# AB_Amplifier.net
KiCad netlist of a schematic drawn in Altium Designer
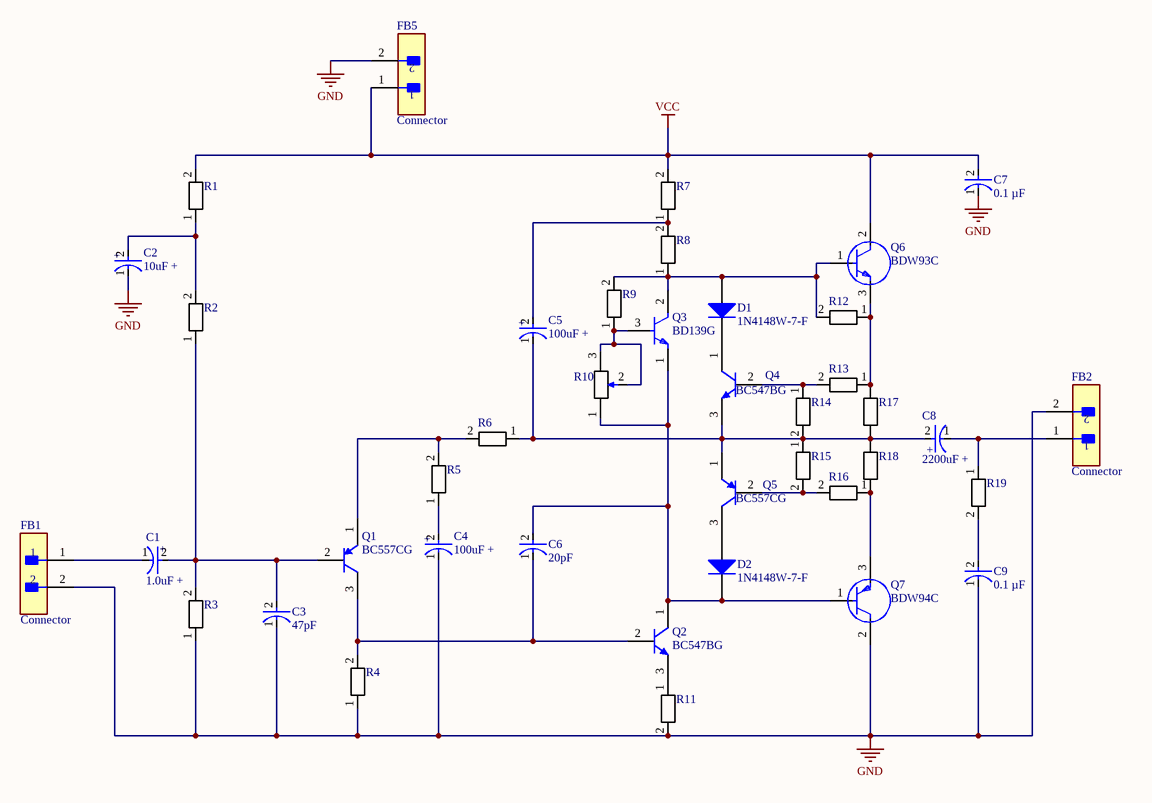
[diagram p0: AB_Amplifier.SchDoc]

(export (version "E")
  (design (tool "Eeschema 10.0.6"))
  (components
    (comp (ref "C1")
      (value "1.0uF +")
      (footprint "106CKR050M")
      (libsource (lib "AB-Amplifier") (part "Elco - 1.0uF"))
    )
    (comp (ref "C2")
      (value "10uF +")
      (footprint "106CKR050M")
      (libsource (lib "AB-Amplifier") (part "Elco - 10uF"))
    )
    (comp (ref "C3")
      (value "47pF")
      (footprint "0805")
      (libsource (lib "AB-Amplifier") (part "Capasitor - 0805"))
    )
    (comp (ref "C4")
      (value "100uF +")
      (footprint "107CKR050M")
      (libsource (lib "AB-Amplifier") (part "Elco - 100uF"))
    )
    (comp (ref "C5")
      (value "100uF +")
      (footprint "107CKR050M")
      (libsource (lib "AB-Amplifier") (part "Elco - 100uF"))
    )
    (comp (ref "C6")
      (value "20pF")
      (footprint "0805")
      (libsource (lib "AB-Amplifier") (part "Capasitor - 0805"))
    )
    (comp (ref "C7")
      (value "0.1 µF")
      (footprint "0805")
      (libsource (lib "AB-Amplifier") (part "Capasitor - 0805"))
    )
    (comp (ref "C8")
      (value "2200uF +")
      (footprint "2200cap")
      (libsource (lib "AB-Amplifier") (part "Elco - 2000uF"))
    )
    (comp (ref "C9")
      (value "0.1 µF")
      (footprint "0805")
      (libsource (lib "AB-Amplifier") (part "Capasitor - 0805"))
    )
    (comp (ref "D1")
      (value "1N4148W-7-F")
      (footprint "1N4148")
      (description "Fast Switching Diode, 100 V, 0.15 A, -65 to 150 degC, 2-Pin?SOD123, RoHS, Tape and Reel")
      (fields (field (name "MANUFACTURER") "DiodesIncorporated"))
      (libsource (lib "AB-Amplifier") (part "Diode - 1N4148"))
    )
    (comp (ref "D2")
      (value "1N4148W-7-F")
      (footprint "1N4148")
      (description "Fast Switching Diode, 100 V, 0.15 A, -65 to 150 degC, 2-Pin?SOD123, RoHS, Tape and Reel")
      (fields (field (name "MANUFACTURER") "DiodesIncorporated"))
      (libsource (lib "AB-Amplifier") (part "Diode - 1N4148"))
    )
    (comp (ref "FB1")
      (value "Connector")
      (footprint "AB-Amplifier:Connector")
      (description "Ferrite Bead")
      (fields
        (field (name "MANUFACTURER_PART_NUMBER") "ACML-0805-500-T")
        (field (name "MOUSER PART NUMBER") "815-ACML-0805-500T")
      )
      (libsource (lib "") (part "Connector_1"))
    )
    (comp (ref "FB2")
      (value "Connector")
      (footprint "AB-Amplifier:Connector")
      (description "Ferrite Bead")
      (fields
        (field (name "MANUFACTURER_PART_NUMBER") "ACML-0805-500-T")
        (field (name "MOUSER PART NUMBER") "815-ACML-0805-500T")
      )
      (libsource (lib "AB-Amplifier") (part "Connector"))
    )
    (comp (ref "FB5")
      (value "Connector")
      (footprint "AB-Amplifier:Connector")
      (description "Ferrite Bead")
      (fields
        (field (name "MANUFACTURER_PART_NUMBER") "ACML-0805-500-T")
        (field (name "MOUSER PART NUMBER") "815-ACML-0805-500T")
      )
      (libsource (lib "AB-Amplifier") (part "Connector"))
    )
    (comp (ref "Q1")
      (value "BC557CG")
      (footprint "BC557")
      (description "Amplifier Transistor, PNP Silicon, 3-Pin TO-92, Pb-Free, Bulk Box")
      (fields (field (name "MANUFACTURER") "On Semiconductor"))
      (libsource (lib "AB-Amplifier") (part "Transistor - BC557_1"))
    )
    (comp (ref "Q2")
      (value "BC547BG")
      (footprint "BC547")
      (description "Amplifier Transistor, NPN Silicon, 3-Pin TO-92, Pb-Free, Bulk Box")
      (fields (field (name "MANUFACTURER") "On Semiconductor"))
      (libsource (lib "AB-Amplifier") (part "Transistor - BC547_1"))
    )
    (comp (ref "Q3")
      (value "BD139G")
      (footprint "BD139")
      (libsource (lib "AB-Amplifier") (part "Transistor - BD139"))
    )
    (comp (ref "Q4")
      (value "BC547BG")
      (footprint "BC547")
      (description "Amplifier Transistor, NPN Silicon, 3-Pin TO-92, Pb-Free, Bulk Box")
      (fields (field (name "MANUFACTURER") "On Semiconductor"))
      (libsource (lib "AB-Amplifier") (part "Transistor - BC547"))
    )
    (comp (ref "Q5")
      (value "BC557CG")
      (footprint "BC557")
      (description "Amplifier Transistor, PNP Silicon, 3-Pin TO-92, Pb-Free, Bulk Box")
      (fields (field (name "MANUFACTURER") "On Semiconductor"))
      (libsource (lib "AB-Amplifier") (part "Transistor - BC557"))
    )
    (comp (ref "Q6")
      (value "BDW93C")
      (footprint "BDW94C")
      (description "BDW93C BDW93C Series 100 V 12 A 80 W NPN Darlington Transistor - TO-220-3")
      (libsource (lib "AB-Amplifier") (part "Transistor - BDW93C"))
    )
    (comp (ref "Q7")
      (value "BDW94C")
      (footprint "AB-Amplifier:BDW94C")
      (description "Transistor BJT PNP")
      (fields (field (name "MOUSER PART NUMBER") "511-BDW94C"))
      (libsource (lib "AB-Amplifier") (part "Transistor - BDW94C"))
    )
    (comp (ref "R1")
      (value "CRCW080510R0FKEA")
      (footprint "0805")
      (fields (field (name "MANUFACTURER") "Vishay Dale"))
      (libsource (lib "AB-Amplifier") (part "Resistor 0805"))
    )
    (comp (ref "R2")
      (value "CRCW080510R0FKEA")
      (footprint "0805")
      (fields (field (name "MANUFACTURER") "Vishay Dale"))
      (libsource (lib "AB-Amplifier") (part "Resistor 0805"))
    )
    (comp (ref "R3")
      (value "CRCW080510R0FKEA")
      (footprint "0805")
      (fields (field (name "MANUFACTURER") "Vishay Dale"))
      (libsource (lib "AB-Amplifier") (part "Resistor 0805"))
    )
    (comp (ref "R4")
      (value "CRCW080510R0FKEA")
      (footprint "0805")
      (fields (field (name "MANUFACTURER") "Vishay Dale"))
      (libsource (lib "AB-Amplifier") (part "Resistor 0805"))
    )
    (comp (ref "R5")
      (value "CRCW080510R0FKEA")
      (footprint "0805")
      (fields (field (name "MANUFACTURER") "Vishay Dale"))
      (libsource (lib "AB-Amplifier") (part "Resistor 0805"))
    )
    (comp (ref "R6")
      (value "CRCW080510R0FKEA")
      (footprint "0805")
      (fields (field (name "MANUFACTURER") "Vishay Dale"))
      (libsource (lib "AB-Amplifier") (part "Resistor 0805"))
    )
    (comp (ref "R7")
      (value "CRCW080510R0FKEA")
      (footprint "0805")
      (fields (field (name "MANUFACTURER") "Vishay Dale"))
      (libsource (lib "AB-Amplifier") (part "Resistor 0805"))
    )
    (comp (ref "R8")
      (value "CRCW080510R0FKEA")
      (footprint "0805")
      (fields (field (name "MANUFACTURER") "Vishay Dale"))
      (libsource (lib "AB-Amplifier") (part "Resistor 0805"))
    )
    (comp (ref "R9")
      (value "CRCW080510R0FKEA")
      (footprint "0805")
      (fields (field (name "MANUFACTURER") "Vishay Dale"))
      (libsource (lib "AB-Amplifier") (part "Resistor 0805"))
    )
    (comp (ref "R10")
      (value "249FGJSPXB25503KA")
      (footprint "Potentiometer 15mm")
      (fields (field (name "TOLERANCE") "10%"))
      (libsource (lib "AB-Amplifier") (part "Potentiometer"))
    )
    (comp (ref "R11")
      (value "CRCW080510R0FKEA")
      (footprint "0805")
      (fields (field (name "MANUFACTURER") "Vishay Dale"))
      (libsource (lib "AB-Amplifier") (part "Resistor 0805"))
    )
    (comp (ref "R12")
      (value "CRCW080510R0FKEA")
      (footprint "0805")
      (fields (field (name "MANUFACTURER") "Vishay Dale"))
      (libsource (lib "AB-Amplifier") (part "Resistor 0805"))
    )
    (comp (ref "R13")
      (value "CRCW080510R0FKEA")
      (footprint "0805")
      (fields (field (name "MANUFACTURER") "Vishay Dale"))
      (libsource (lib "AB-Amplifier") (part "Resistor 0805"))
    )
    (comp (ref "R14")
      (value "CRCW080510R0FKEA")
      (footprint "0805")
      (fields (field (name "MANUFACTURER") "Vishay Dale"))
      (libsource (lib "AB-Amplifier") (part "Resistor 0805"))
    )
    (comp (ref "R15")
      (value "CRCW080510R0FKEA")
      (footprint "0805")
      (fields (field (name "MANUFACTURER") "Vishay Dale"))
      (libsource (lib "AB-Amplifier") (part "Resistor 0805"))
    )
    (comp (ref "R16")
      (value "CRCW080510R0FKEA")
      (footprint "0805")
      (fields (field (name "MANUFACTURER") "Vishay Dale"))
      (libsource (lib "AB-Amplifier") (part "Resistor 0805"))
    )
    (comp (ref "R17")
      (value "RK73B2ATTD224J")
      (footprint "0.33 1W")
      (fields (field (name "MANUFACTURER") "KOA Speer"))
      (libsource (lib "AB-Amplifier") (part "Resistor - 1W Through Hole"))
    )
    (comp (ref "R18")
      (value "RK73B2ATTD224J")
      (footprint "0.33 1W")
      (fields (field (name "MANUFACTURER") "KOA Speer"))
      (libsource (lib "AB-Amplifier") (part "Resistor - 1W Through Hole"))
    )
    (comp (ref "R19")
      (value "CRCW080510R0FKEA")
      (footprint "0805")
      (fields (field (name "MANUFACTURER") "Vishay Dale"))
      (libsource (lib "AB-Amplifier") (part "Resistor 0805"))
    )
  )
  (nets
    (net (code "1") (name "GND") (class "Default")
      (node (ref "C2") (pin "1") (pinfunction "C_1") (pintype "passive"))
      (node (ref "C3") (pin "1") (pinfunction "C_1") (pintype "passive"))
      (node (ref "C4") (pin "1") (pinfunction "C_1") (pintype "passive"))
      (node (ref "C7") (pin "1") (pinfunction "C_1") (pintype "passive"))
      (node (ref "C9") (pin "1") (pinfunction "C_1") (pintype "passive"))
      (node (ref "FB1") (pin "2") (pinfunction "2_2") (pintype "passive"))
      (node (ref "FB2") (pin "2") (pinfunction "2_2") (pintype "passive"))
      (node (ref "FB5") (pin "2") (pinfunction "2_2") (pintype "passive"))
      (node (ref "Q7") (pin "2") (pinfunction "C_2") (pintype "passive"))
      (node (ref "R11") (pin "2") (pinfunction "2_2") (pintype "passive"))
      (node (ref "R3") (pin "1") (pinfunction "1_1") (pintype "passive"))
      (node (ref "R4") (pin "1") (pinfunction "1_1") (pintype "passive"))
    )
    (net (code "2") (name "Net-(C1-A)") (class "Default")
      (node (ref "C1") (pin "2") (pinfunction "A_2") (pintype "passive"))
      (node (ref "C3") (pin "2") (pinfunction "A_2") (pintype "passive"))
      (node (ref "Q1") (pin "2") (pinfunction "B_2") (pintype "passive"))
      (node (ref "R2") (pin "1") (pinfunction "1_1") (pintype "passive"))
      (node (ref "R3") (pin "2") (pinfunction "2_2") (pintype "passive"))
    )
    (net (code "3") (name "Net-(C1-C)") (class "Default")
      (node (ref "C1") (pin "1") (pinfunction "C_1") (pintype "passive"))
      (node (ref "FB1") (pin "1") (pinfunction "1_1") (pintype "passive"))
    )
    (net (code "4") (name "Net-(C2-A)") (class "Default")
      (node (ref "C2") (pin "2") (pinfunction "A_2") (pintype "passive"))
      (node (ref "R1") (pin "1") (pinfunction "1_1") (pintype "passive"))
      (node (ref "R2") (pin "2") (pinfunction "2_2") (pintype "passive"))
    )
    (net (code "5") (name "Net-(C4-A)") (class "Default")
      (node (ref "C4") (pin "2") (pinfunction "A_2") (pintype "passive"))
      (node (ref "R5") (pin "1") (pinfunction "1_1") (pintype "passive"))
    )
    (net (code "6") (name "Net-(C5-A)") (class "Default")
      (node (ref "C5") (pin "2") (pinfunction "A_2") (pintype "passive"))
      (node (ref "R7") (pin "1") (pinfunction "1_1") (pintype "passive"))
      (node (ref "R8") (pin "2") (pinfunction "2_2") (pintype "passive"))
    )
    (net (code "7") (name "Net-(C5-C)") (class "Default")
      (node (ref "C5") (pin "1") (pinfunction "C_1") (pintype "passive"))
      (node (ref "C8") (pin "2") (pinfunction "A_2") (pintype "passive"))
      (node (ref "Q4") (pin "3") (pinfunction "E_3") (pintype "passive"))
      (node (ref "Q5") (pin "1") (pinfunction "E_1") (pintype "passive"))
      (node (ref "R14") (pin "2") (pinfunction "2_2") (pintype "passive"))
      (node (ref "R15") (pin "1") (pinfunction "1_1") (pintype "passive"))
      (node (ref "R17") (pin "1") (pinfunction "1_1") (pintype "passive"))
      (node (ref "R18") (pin "2") (pinfunction "2_2") (pintype "passive"))
      (node (ref "R6") (pin "1") (pinfunction "1_1") (pintype "passive"))
    )
    (net (code "8") (name "Net-(C6-A)") (class "Default")
      (node (ref "C6") (pin "2") (pinfunction "A_2") (pintype "passive"))
      (node (ref "D2") (pin "2") (pinfunction "K_2") (pintype "passive"))
      (node (ref "Q2") (pin "1") (pinfunction "C_1") (pintype "passive"))
      (node (ref "Q3") (pin "1") (pinfunction "E_1") (pintype "passive"))
      (node (ref "Q7") (pin "1") (pinfunction "B_1") (pintype "passive"))
      (node (ref "R10") (pin "1") (pinfunction "1_1") (pintype "passive"))
    )
    (net (code "9") (name "Net-(C6-C)") (class "Default")
      (node (ref "C6") (pin "1") (pinfunction "C_1") (pintype "passive"))
      (node (ref "Q1") (pin "3") (pinfunction "E_3") (pintype "passive"))
      (node (ref "Q2") (pin "2") (pinfunction "B_2") (pintype "passive"))
      (node (ref "R4") (pin "2") (pinfunction "2_2") (pintype "passive"))
    )
    (net (code "10") (name "Net-(C8-C)") (class "Default")
      (node (ref "C8") (pin "1") (pinfunction "C_1") (pintype "passive"))
      (node (ref "FB2") (pin "1") (pinfunction "1_1") (pintype "passive"))
      (node (ref "R19") (pin "1") (pinfunction "1_1") (pintype "passive"))
    )
    (net (code "11") (name "Net-(C9-A)") (class "Default")
      (node (ref "C9") (pin "2") (pinfunction "A_2") (pintype "passive"))
      (node (ref "R19") (pin "2") (pinfunction "2_2") (pintype "passive"))
    )
    (net (code "12") (name "Net-(D1-A)") (class "Default")
      (node (ref "D1") (pin "1") (pinfunction "A_1") (pintype "passive"))
      (node (ref "Q3") (pin "2") (pinfunction "C_2") (pintype "passive"))
      (node (ref "Q6") (pin "1") (pinfunction "B_1") (pintype "passive"))
      (node (ref "R12") (pin "2") (pinfunction "2_2") (pintype "passive"))
      (node (ref "R8") (pin "1") (pinfunction "1_1") (pintype "passive"))
      (node (ref "R9") (pin "2") (pinfunction "2_2") (pintype "passive"))
    )
    (net (code "13") (name "Net-(D1-K)") (class "Default")
      (node (ref "D1") (pin "2") (pinfunction "K_2") (pintype "passive"))
      (node (ref "Q4") (pin "1") (pinfunction "C_1") (pintype "passive"))
    )
    (net (code "14") (name "Net-(D2-A)") (class "Default")
      (node (ref "D2") (pin "1") (pinfunction "A_1") (pintype "passive"))
      (node (ref "Q5") (pin "3") (pinfunction "C_3") (pintype "passive"))
    )
    (net (code "15") (name "Net-(Q1-C)") (class "Default")
      (node (ref "Q1") (pin "1") (pinfunction "C_1") (pintype "passive"))
      (node (ref "R5") (pin "2") (pinfunction "2_2") (pintype "passive"))
      (node (ref "R6") (pin "2") (pinfunction "2_2") (pintype "passive"))
    )
    (net (code "16") (name "Net-(Q2-E)") (class "Default")
      (node (ref "Q2") (pin "3") (pinfunction "E_3") (pintype "passive"))
      (node (ref "R11") (pin "1") (pinfunction "1_1") (pintype "passive"))
    )
    (net (code "17") (name "Net-(Q3-B)") (class "Default")
      (node (ref "Q3") (pin "3") (pinfunction "B_3") (pintype "passive"))
      (node (ref "R10") (pin "2") (pintype "passive"))
      (node (ref "R10") (pin "3") (pinfunction "3_3") (pintype "passive"))
      (node (ref "R9") (pin "1") (pinfunction "1_1") (pintype "passive"))
    )
    (net (code "18") (name "Net-(Q4-B)") (class "Default")
      (node (ref "Q4") (pin "2") (pinfunction "B_2") (pintype "passive"))
      (node (ref "R13") (pin "2") (pinfunction "2_2") (pintype "passive"))
      (node (ref "R14") (pin "1") (pinfunction "1_1") (pintype "passive"))
    )
    (net (code "19") (name "Net-(Q5-B)") (class "Default")
      (node (ref "Q5") (pin "2") (pinfunction "B_2") (pintype "passive"))
      (node (ref "R15") (pin "2") (pinfunction "2_2") (pintype "passive"))
      (node (ref "R16") (pin "2") (pinfunction "2_2") (pintype "passive"))
    )
    (net (code "20") (name "Net-(Q6-E)") (class "Default")
      (node (ref "Q6") (pin "3") (pinfunction "E_3") (pintype "passive"))
      (node (ref "R12") (pin "1") (pinfunction "1_1") (pintype "passive"))
      (node (ref "R13") (pin "1") (pinfunction "1_1") (pintype "passive"))
      (node (ref "R17") (pin "2") (pinfunction "2_2") (pintype "passive"))
    )
    (net (code "21") (name "Net-(Q7-E)") (class "Default")
      (node (ref "Q7") (pin "3") (pinfunction "E_3") (pintype "passive"))
      (node (ref "R16") (pin "1") (pinfunction "1_1") (pintype "passive"))
      (node (ref "R18") (pin "1") (pinfunction "1_1") (pintype "passive"))
    )
    (net (code "22") (name "VCC") (class "Default")
      (node (ref "C7") (pin "2") (pinfunction "A_2") (pintype "passive"))
      (node (ref "FB5") (pin "1") (pinfunction "1_1") (pintype "passive"))
      (node (ref "Q6") (pin "2") (pinfunction "C_2") (pintype "passive"))
      (node (ref "R1") (pin "2") (pinfunction "2_2") (pintype "passive"))
      (node (ref "R7") (pin "2") (pinfunction "2_2") (pintype "passive"))
    )
  )
)
